# RTI-Dome.net
KiCad netlist of a schematic drawn in EAGLE
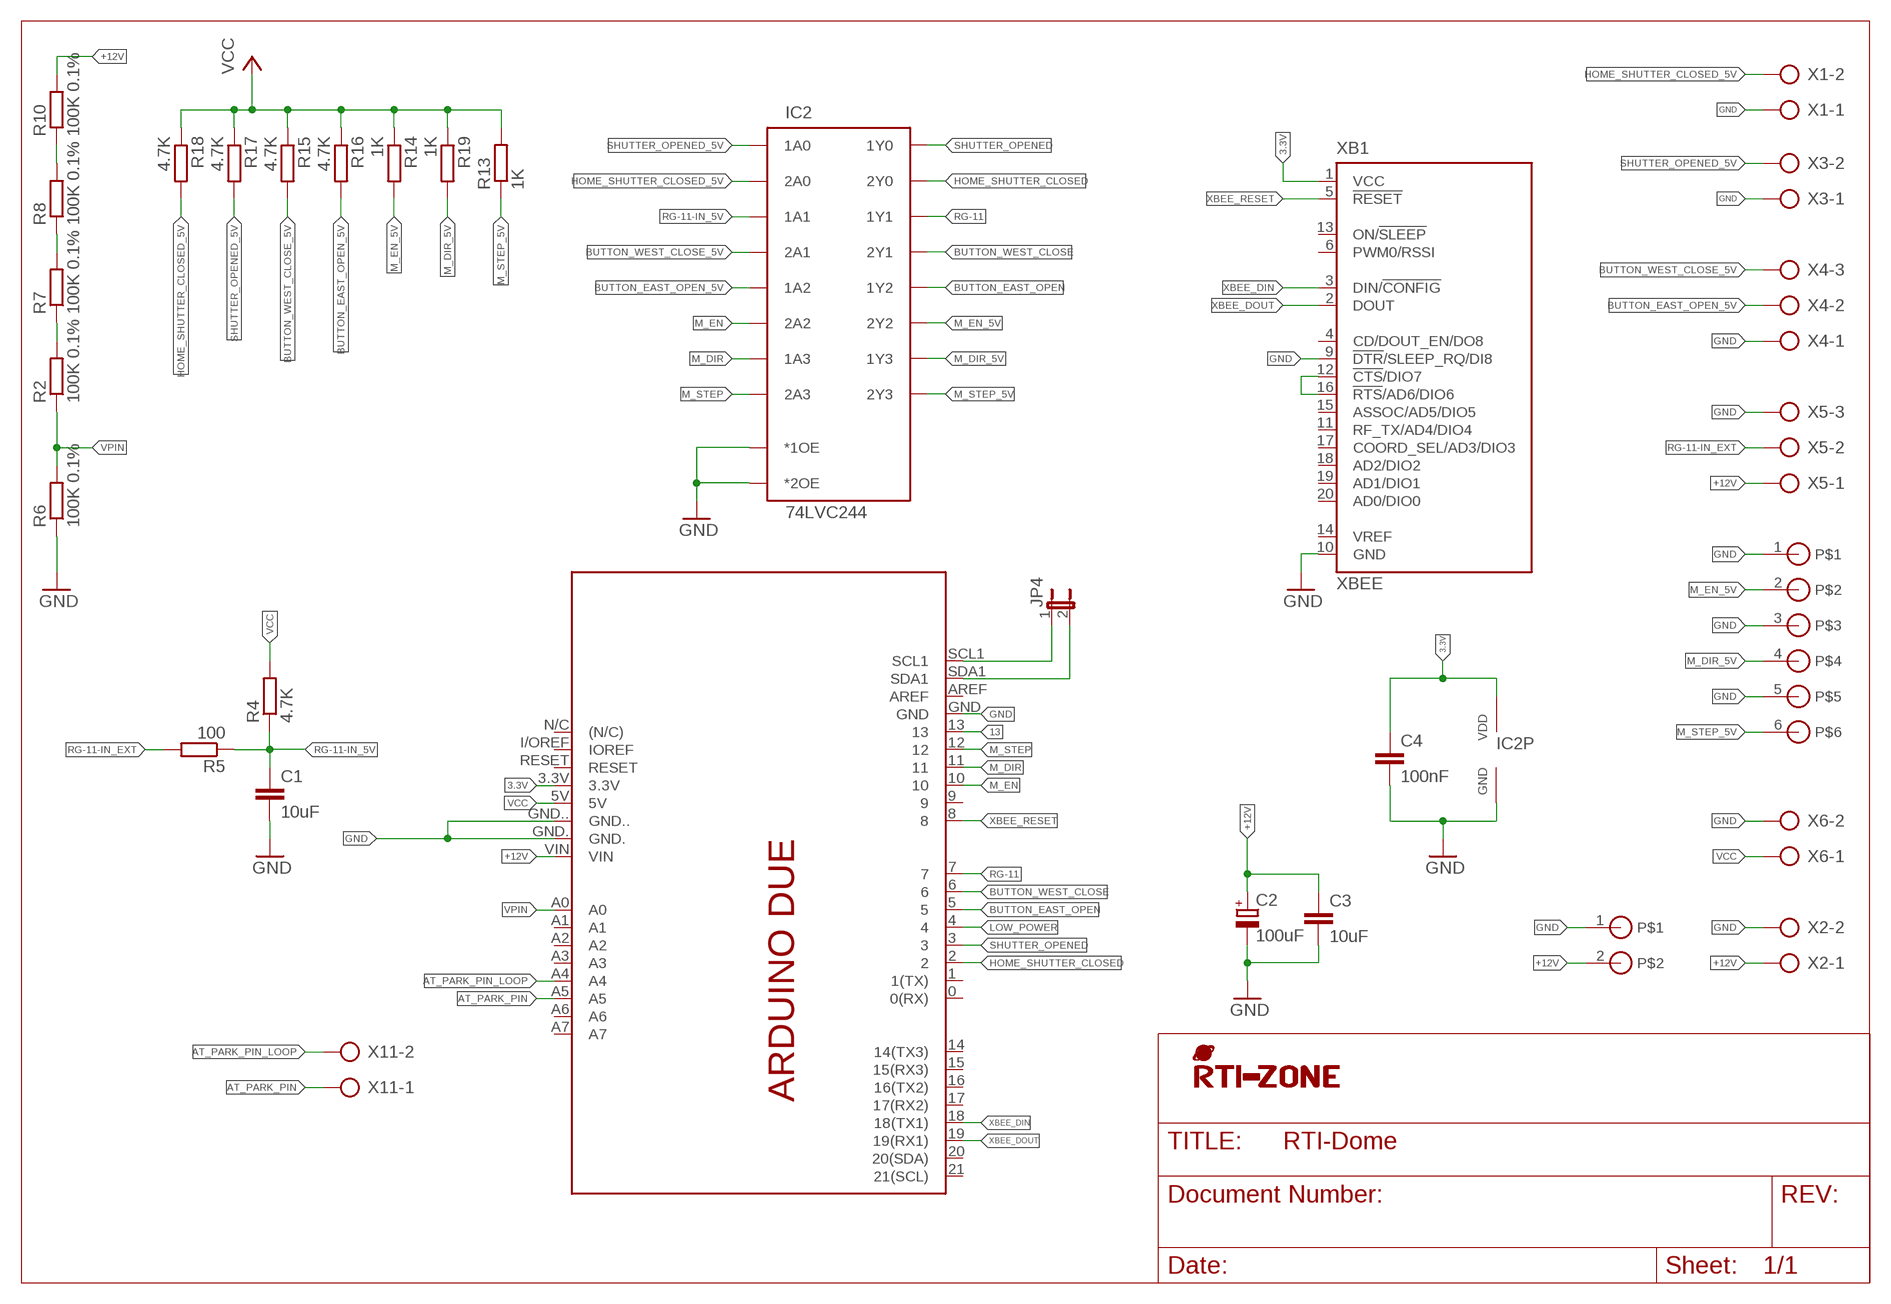
[diagram p0: schematic, sheet 1]

(export (version "E")
  (design (tool "Eeschema 10.0.6"))
  (components
    (comp (ref "C1")
      (value "10uF")
      (footprint "eagle-import:C0805")
      (libsource (lib "eagle-import") (part "C-EU'0805'"))
    )
    (comp (ref "C2")
      (value "100uF")
      (footprint "eagle-import:UD-10X10_NICHICON")
      (libsource (lib "eagle-import") (part "CPOL-EU"))
    )
    (comp (ref "C3")
      (value "10uF")
      (footprint "eagle-import:C0805")
      (libsource (lib "eagle-import") (part "C-EU'0805'"))
    )
    (comp (ref "C4")
      (value "100nF")
      (footprint "eagle-import:C0805")
      (libsource (lib "eagle-import") (part "C-EU'0805'"))
    )
    (comp (ref "IC2")
      (value "74LVC244")
      (footprint "eagle-import:TSSOP20")
      (libsource (lib "eagle-import") (part "74244LVC"))
    )
    (comp (ref "JP4")
      (value "JP1E")
      (footprint "eagle-import:JP1")
      (libsource (lib "eagle-import") (part "JP1E"))
    )
    (comp (ref "PCB1")
      (value "ARDUINO_DUE_SHIELD_SHORT")
      (footprint "eagle-import:ARDUINO_DUE_SHIELD_SHORT")
      (libsource (lib "eagle-import") (part "ARDUINO_DUE_SHIELD_SHORT"))
    )
    (comp (ref "R2")
      (value "100K 0.1%")
      (footprint "eagle-import:R0805")
      (libsource (lib "eagle-import") (part "R-EU'0805'"))
    )
    (comp (ref "R4")
      (value "4.7K")
      (footprint "eagle-import:R0805")
      (libsource (lib "eagle-import") (part "R-EU'0805'"))
    )
    (comp (ref "R5")
      (value "100")
      (footprint "eagle-import:R0805")
      (libsource (lib "eagle-import") (part "R-EU'0805'"))
    )
    (comp (ref "R6")
      (value "100K 0.1%")
      (footprint "eagle-import:R0805")
      (libsource (lib "eagle-import") (part "R-EU'0805'"))
    )
    (comp (ref "R7")
      (value "100K 0.1%")
      (footprint "eagle-import:R0805")
      (libsource (lib "eagle-import") (part "R-EU'0805'"))
    )
    (comp (ref "R8")
      (value "100K 0.1%")
      (footprint "eagle-import:R0805")
      (libsource (lib "eagle-import") (part "R-EU'0805'"))
    )
    (comp (ref "R10")
      (value "100K 0.1%")
      (footprint "eagle-import:R0805")
      (libsource (lib "eagle-import") (part "R-EU'0805'"))
    )
    (comp (ref "R13")
      (value "1K")
      (footprint "eagle-import:R0805")
      (libsource (lib "eagle-import") (part "R-EU'0805'"))
    )
    (comp (ref "R14")
      (value "1K")
      (footprint "eagle-import:R0805")
      (libsource (lib "eagle-import") (part "R-EU'0805'"))
    )
    (comp (ref "R15")
      (value "4.7K")
      (footprint "eagle-import:R0805")
      (libsource (lib "eagle-import") (part "R-EU'0805'"))
    )
    (comp (ref "R16")
      (value "4.7K")
      (footprint "eagle-import:R0805")
      (libsource (lib "eagle-import") (part "R-EU'0805'"))
    )
    (comp (ref "R17")
      (value "4.7K")
      (footprint "eagle-import:R0805")
      (libsource (lib "eagle-import") (part "R-EU'0805'"))
    )
    (comp (ref "R18")
      (value "4.7K")
      (footprint "eagle-import:R0805")
      (libsource (lib "eagle-import") (part "R-EU'0805'"))
    )
    (comp (ref "R19")
      (value "1K")
      (footprint "eagle-import:R0805")
      (libsource (lib "eagle-import") (part "R-EU'0805'"))
    )
    (comp (ref "U$2")
      (value "STL-140-2")
      (footprint "eagle-import:STL-140-2")
      (libsource (lib "eagle-import") (part "STL-140-2"))
    )
    (comp (ref "U$3")
      (value "STL-140-6")
      (footprint "eagle-import:STL-140-6")
      (libsource (lib "eagle-import") (part "STL-140-6"))
    )
    (comp (ref "U$4")
      (value "RTI-LOGO_BIG")
      (footprint "eagle-import:LOGO_BIG")
      (libsource (lib "eagle-import") (part "RTI-LOGO_BIG"))
    )
    (comp (ref "X1")
      (value "AK500/2")
      (footprint "eagle-import:AK500_2")
      (libsource (lib "eagle-import") (part "AK500/2"))
    )
    (comp (ref "X2")
      (value "AK500/2")
      (footprint "eagle-import:AK500_2")
      (libsource (lib "eagle-import") (part "AK500/2"))
    )
    (comp (ref "X3")
      (value "AK500/2")
      (footprint "eagle-import:AK500_2")
      (libsource (lib "eagle-import") (part "AK500/2"))
    )
    (comp (ref "X4")
      (value "AK500/3")
      (footprint "eagle-import:AK500_3")
      (libsource (lib "eagle-import") (part "AK500/3"))
    )
    (comp (ref "X5")
      (value "AK500/3")
      (footprint "eagle-import:AK500_3")
      (libsource (lib "eagle-import") (part "AK500/3"))
    )
    (comp (ref "X6")
      (value "AK500/2")
      (footprint "eagle-import:AK500_2")
      (libsource (lib "eagle-import") (part "AK500/2"))
    )
    (comp (ref "X11")
      (value "AK500/2")
      (footprint "eagle-import:AK500_2")
      (libsource (lib "eagle-import") (part "AK500/2"))
    )
    (comp (ref "XB1")
      (value "XBEE")
      (footprint "eagle-import:XBEE")
      (fields (field (name "MPN") "XBP24-Z7UIT-004"))
      (libsource (lib "eagle-import") (part "XBEE"))
    )
  )
  (nets
    (net (code "1") (name "+12V") (class "Default")
      (node (ref "C2") (pin "+") (pinfunction "+_+") (pintype "passive"))
      (node (ref "C3") (pin "1") (pinfunction "1_1") (pintype "passive"))
      (node (ref "PCB1") (pin "VIN") (pinfunction "VIN_VIN") (pintype "bidirectional"))
      (node (ref "R10") (pin "2") (pinfunction "2_2") (pintype "passive"))
      (node (ref "U$2") (pin "2") (pinfunction "P$2_2") (pintype "bidirectional"))
      (node (ref "X2") (pin "1") (pinfunction "KL_1") (pintype "passive"))
      (node (ref "X5") (pin "1") (pinfunction "KL_1") (pintype "passive"))
    )
    (net (code "2") (name "3.3V") (class "Default")
      (node (ref "C4") (pin "1") (pinfunction "1_1") (pintype "passive"))
      (node (ref "IC2") (pin "P$20") (pinfunction "VDD_P$20") (pintype "power_in"))
      (node (ref "PCB1") (pin "3.3V") (pinfunction "3.3V_3.3V") (pintype "bidirectional"))
      (node (ref "XB1") (pin "1") (pinfunction "VCC_1") (pintype "power_in"))
    )
    (net (code "3") (name "13") (class "Default")
      (node (ref "PCB1") (pin "13") (pinfunction "13_13") (pintype "bidirectional"))
    )
    (net (code "4") (name "AT_PARK_PIN") (class "Default")
      (node (ref "PCB1") (pin "A5") (pinfunction "A5_A5") (pintype "bidirectional"))
      (node (ref "X11") (pin "1") (pinfunction "KL_1") (pintype "passive"))
    )
    (net (code "5") (name "AT_PARK_PIN_LOOP") (class "Default")
      (node (ref "PCB1") (pin "A4") (pinfunction "A4_A4") (pintype "bidirectional"))
      (node (ref "X11") (pin "2") (pinfunction "KL_2") (pintype "passive"))
    )
    (net (code "6") (name "BUTTON_EAST_OPEN") (class "Default")
      (node (ref "IC2") (pin "P$14") (pinfunction "1Y2_P$14") (pintype "output"))
      (node (ref "PCB1") (pin "5") (pinfunction "5_5") (pintype "bidirectional"))
    )
    (net (code "7") (name "BUTTON_EAST_OPEN_5V") (class "Default")
      (node (ref "IC2") (pin "P$6") (pinfunction "1A2_P$6") (pintype "input"))
      (node (ref "R16") (pin "2") (pinfunction "2_2") (pintype "passive"))
      (node (ref "X4") (pin "2") (pinfunction "KL_2") (pintype "passive"))
    )
    (net (code "8") (name "BUTTON_WEST_CLOSE") (class "Default")
      (node (ref "IC2") (pin "P$5") (pinfunction "2Y1_P$5") (pintype "output"))
      (node (ref "PCB1") (pin "6") (pinfunction "6_6") (pintype "bidirectional"))
    )
    (net (code "9") (name "BUTTON_WEST_CLOSE_5V") (class "Default")
      (node (ref "IC2") (pin "P$15") (pinfunction "2A1_P$15") (pintype "input"))
      (node (ref "R15") (pin "2") (pinfunction "2_2") (pintype "passive"))
      (node (ref "X4") (pin "3") (pinfunction "KL_3") (pintype "passive"))
    )
    (net (code "10") (name "GND") (class "Default")
      (node (ref "C1") (pin "2") (pinfunction "2_2") (pintype "passive"))
      (node (ref "C2") (pin "-") (pinfunction "-_-") (pintype "passive"))
      (node (ref "C3") (pin "2") (pinfunction "2_2") (pintype "passive"))
      (node (ref "C4") (pin "2") (pinfunction "2_2") (pintype "passive"))
      (node (ref "IC2") (pin "P$1") (pinfunction "*1OE_P$1") (pintype "input"))
      (node (ref "IC2") (pin "P$10") (pinfunction "GND_P$10") (pintype "power_in"))
      (node (ref "IC2") (pin "P$19") (pinfunction "*2OE_P$19") (pintype "input"))
      (node (ref "PCB1") (pin "GND") (pinfunction "GND_GND") (pintype "bidirectional"))
      (node (ref "PCB1") (pin "GND.") (pinfunction "GND._GND.") (pintype "bidirectional"))
      (node (ref "PCB1") (pin "GND..") (pinfunction "GND.._GND..") (pintype "bidirectional"))
      (node (ref "R6") (pin "1") (pinfunction "1_1") (pintype "passive"))
      (node (ref "U$2") (pin "1") (pinfunction "P$1_1") (pintype "bidirectional"))
      (node (ref "U$3") (pin "1") (pinfunction "P$1_1") (pintype "bidirectional"))
      (node (ref "U$3") (pin "3") (pinfunction "P$3_3") (pintype "bidirectional"))
      (node (ref "U$3") (pin "5") (pinfunction "P$5_5") (pintype "bidirectional"))
      (node (ref "X1") (pin "1") (pinfunction "KL_1") (pintype "passive"))
      (node (ref "X2") (pin "2") (pinfunction "KL_2") (pintype "passive"))
      (node (ref "X3") (pin "1") (pinfunction "KL_1") (pintype "passive"))
      (node (ref "X4") (pin "1") (pinfunction "KL_1") (pintype "passive"))
      (node (ref "X5") (pin "3") (pinfunction "KL_3") (pintype "passive"))
      (node (ref "X6") (pin "2") (pinfunction "KL_2") (pintype "passive"))
      (node (ref "XB1") (pin "10") (pinfunction "GND_10") (pintype "power_in"))
      (node (ref "XB1") (pin "9") (pinfunction "~{DTR}/SLEEP_RQ/DI8_9") (pintype "bidirectional"))
    )
    (net (code "11") (name "HOME_SHUTTER_CLOSED") (class "Default")
      (node (ref "IC2") (pin "P$3") (pinfunction "2Y0_P$3") (pintype "output"))
      (node (ref "PCB1") (pin "2") (pinfunction "2_2") (pintype "bidirectional"))
    )
    (net (code "12") (name "HOME_SHUTTER_CLOSED_5V") (class "Default")
      (node (ref "IC2") (pin "P$17") (pinfunction "2A0_P$17") (pintype "input"))
      (node (ref "R18") (pin "2") (pinfunction "2_2") (pintype "passive"))
      (node (ref "X1") (pin "2") (pinfunction "KL_2") (pintype "passive"))
    )
    (net (code "13") (name "LOW_POWER") (class "Default")
      (node (ref "PCB1") (pin "4") (pinfunction "4_4") (pintype "bidirectional"))
    )
    (net (code "14") (name "M_DIR") (class "Default")
      (node (ref "IC2") (pin "P$8") (pinfunction "1A3_P$8") (pintype "input"))
      (node (ref "PCB1") (pin "11") (pinfunction "11_11") (pintype "bidirectional"))
    )
    (net (code "15") (name "M_DIR_5V") (class "Default")
      (node (ref "IC2") (pin "P$12") (pinfunction "1Y3_P$12") (pintype "output"))
      (node (ref "R19") (pin "2") (pinfunction "2_2") (pintype "passive"))
      (node (ref "U$3") (pin "4") (pinfunction "P$4_4") (pintype "bidirectional"))
    )
    (net (code "16") (name "M_EN") (class "Default")
      (node (ref "IC2") (pin "P$13") (pinfunction "2A2_P$13") (pintype "input"))
      (node (ref "PCB1") (pin "10") (pinfunction "10_10") (pintype "bidirectional"))
    )
    (net (code "17") (name "M_EN_5V") (class "Default")
      (node (ref "IC2") (pin "P$7") (pinfunction "2Y2_P$7") (pintype "output"))
      (node (ref "R14") (pin "2") (pinfunction "2_2") (pintype "passive"))
      (node (ref "U$3") (pin "2") (pinfunction "P$2_2") (pintype "bidirectional"))
    )
    (net (code "18") (name "M_STEP") (class "Default")
      (node (ref "IC2") (pin "P$11") (pinfunction "2A3_P$11") (pintype "input"))
      (node (ref "PCB1") (pin "12") (pinfunction "12_12") (pintype "bidirectional"))
    )
    (net (code "19") (name "M_STEP_5V") (class "Default")
      (node (ref "IC2") (pin "P$9") (pinfunction "2Y3_P$9") (pintype "output"))
      (node (ref "R13") (pin "1") (pinfunction "1_1") (pintype "passive"))
      (node (ref "U$3") (pin "6") (pinfunction "P$6_6") (pintype "bidirectional"))
    )
    (net (code "20") (name "Net-(JP4-Pad1)") (class "Default")
      (node (ref "JP4") (pin "1") (pinfunction "1_1") (pintype "passive"))
      (node (ref "PCB1") (pin "SCL1") (pinfunction "SCL1_SCL1") (pintype "bidirectional"))
    )
    (net (code "21") (name "Net-(JP4-Pad2)") (class "Default")
      (node (ref "JP4") (pin "2") (pinfunction "2_2") (pintype "passive"))
      (node (ref "PCB1") (pin "SDA1") (pinfunction "SDA1_SDA1") (pintype "bidirectional"))
    )
    (net (code "22") (name "Net-(R2-Pad2)") (class "Default")
      (node (ref "R2") (pin "2") (pinfunction "2_2") (pintype "passive"))
      (node (ref "R7") (pin "1") (pinfunction "1_1") (pintype "passive"))
    )
    (net (code "23") (name "Net-(R7-Pad2)") (class "Default")
      (node (ref "R7") (pin "2") (pinfunction "2_2") (pintype "passive"))
      (node (ref "R8") (pin "1") (pinfunction "1_1") (pintype "passive"))
    )
    (net (code "24") (name "Net-(R10-Pad1)") (class "Default")
      (node (ref "R10") (pin "1") (pinfunction "1_1") (pintype "passive"))
      (node (ref "R8") (pin "2") (pinfunction "2_2") (pintype "passive"))
    )
    (net (code "25") (name "Net-(XB1-~{CTS}{slash}DIO7)") (class "Default")
      (node (ref "XB1") (pin "12") (pinfunction "~{CTS}/DIO7_12") (pintype "bidirectional"))
      (node (ref "XB1") (pin "16") (pinfunction "~{RTS}/AD6/DIO6_16") (pintype "bidirectional"))
    )
    (net (code "26") (name "RG-11") (class "Default")
      (node (ref "IC2") (pin "P$16") (pinfunction "1Y1_P$16") (pintype "output"))
      (node (ref "PCB1") (pin "7") (pinfunction "7_7") (pintype "bidirectional"))
    )
    (net (code "27") (name "RG-11-IN_5V") (class "Default")
      (node (ref "C1") (pin "1") (pinfunction "1_1") (pintype "passive"))
      (node (ref "IC2") (pin "P$4") (pinfunction "1A1_P$4") (pintype "input"))
      (node (ref "R4") (pin "1") (pinfunction "1_1") (pintype "passive"))
      (node (ref "R5") (pin "1") (pinfunction "1_1") (pintype "passive"))
    )
    (net (code "28") (name "RG-11-IN_EXT") (class "Default")
      (node (ref "R5") (pin "2") (pinfunction "2_2") (pintype "passive"))
      (node (ref "X5") (pin "2") (pinfunction "KL_2") (pintype "passive"))
    )
    (net (code "29") (name "SHUTTER_OPENED") (class "Default")
      (node (ref "IC2") (pin "P$18") (pinfunction "1Y0_P$18") (pintype "output"))
      (node (ref "PCB1") (pin "3") (pinfunction "3_3") (pintype "bidirectional"))
    )
    (net (code "30") (name "SHUTTER_OPENED_5V") (class "Default")
      (node (ref "IC2") (pin "P$2") (pinfunction "1A0_P$2") (pintype "input"))
      (node (ref "R17") (pin "2") (pinfunction "2_2") (pintype "passive"))
      (node (ref "X3") (pin "2") (pinfunction "KL_2") (pintype "passive"))
    )
    (net (code "31") (name "VCC") (class "Default")
      (node (ref "PCB1") (pin "5V") (pinfunction "5V_5V") (pintype "bidirectional"))
      (node (ref "R13") (pin "2") (pinfunction "2_2") (pintype "passive"))
      (node (ref "R14") (pin "1") (pinfunction "1_1") (pintype "passive"))
      (node (ref "R15") (pin "1") (pinfunction "1_1") (pintype "passive"))
      (node (ref "R16") (pin "1") (pinfunction "1_1") (pintype "passive"))
      (node (ref "R17") (pin "1") (pinfunction "1_1") (pintype "passive"))
      (node (ref "R18") (pin "1") (pinfunction "1_1") (pintype "passive"))
      (node (ref "R19") (pin "1") (pinfunction "1_1") (pintype "passive"))
      (node (ref "R4") (pin "2") (pinfunction "2_2") (pintype "passive"))
      (node (ref "X6") (pin "1") (pinfunction "KL_1") (pintype "passive"))
    )
    (net (code "32") (name "VPIN") (class "Default")
      (node (ref "PCB1") (pin "A0") (pinfunction "A0_A0") (pintype "bidirectional"))
      (node (ref "R2") (pin "1") (pinfunction "1_1") (pintype "passive"))
      (node (ref "R6") (pin "2") (pinfunction "2_2") (pintype "passive"))
    )
    (net (code "33") (name "XBEE_DIN") (class "Default")
      (node (ref "PCB1") (pin "18") (pinfunction "18(TX1)_18") (pintype "bidirectional"))
      (node (ref "XB1") (pin "3") (pinfunction "DIN/~{CONFIG}_3") (pintype "input"))
    )
    (net (code "34") (name "XBEE_DOUT") (class "Default")
      (node (ref "PCB1") (pin "19") (pinfunction "19(RX1)_19") (pintype "bidirectional"))
      (node (ref "XB1") (pin "2") (pinfunction "DOUT_2") (pintype "output"))
    )
    (net (code "35") (name "XBEE_RESET") (class "Default")
      (node (ref "PCB1") (pin "8") (pinfunction "8_8") (pintype "bidirectional"))
      (node (ref "XB1") (pin "5") (pinfunction "~{RESET}_5") (pintype "input"))
    )
    (net (code "36") (name "unconnected-(PCB1-(N{slash}C)-PadN{slash}C)") (class "Default")
      (node (ref "PCB1") (pin "N/C") (pinfunction "(N/C)_N/C") (pintype "bidirectional"))
    )
    (net (code "37") (name "unconnected-(PCB1-0(RX)-Pad0)") (class "Default")
      (node (ref "PCB1") (pin "0") (pinfunction "0(RX)_0") (pintype "bidirectional"))
    )
    (net (code "38") (name "unconnected-(PCB1-1(TX)-Pad1)") (class "Default")
      (node (ref "PCB1") (pin "1") (pinfunction "1(TX)_1") (pintype "bidirectional"))
    )
    (net (code "39") (name "unconnected-(PCB1-14(TX3)-Pad14)") (class "Default")
      (node (ref "PCB1") (pin "14") (pinfunction "14(TX3)_14") (pintype "bidirectional"))
    )
    (net (code "40") (name "unconnected-(PCB1-15(RX3)-Pad15)") (class "Default")
      (node (ref "PCB1") (pin "15") (pinfunction "15(RX3)_15") (pintype "bidirectional"))
    )
    (net (code "41") (name "unconnected-(PCB1-16(TX2)-Pad16)") (class "Default")
      (node (ref "PCB1") (pin "16") (pinfunction "16(TX2)_16") (pintype "bidirectional"))
    )
    (net (code "42") (name "unconnected-(PCB1-17(RX2)-Pad17)") (class "Default")
      (node (ref "PCB1") (pin "17") (pinfunction "17(RX2)_17") (pintype "bidirectional"))
    )
    (net (code "43") (name "unconnected-(PCB1-20(SDA)-Pad20)") (class "Default")
      (node (ref "PCB1") (pin "20") (pinfunction "20(SDA)_20") (pintype "bidirectional"))
    )
    (net (code "44") (name "unconnected-(PCB1-21(SCL)-Pad21)") (class "Default")
      (node (ref "PCB1") (pin "21") (pinfunction "21(SCL)_21") (pintype "bidirectional"))
    )
    (net (code "45") (name "unconnected-(PCB1-IOREF-PadI{slash}OREF)") (class "Default")
      (node (ref "PCB1") (pin "I/OREF") (pinfunction "IOREF_I/OREF") (pintype "bidirectional"))
    )
    (net (code "46") (name "unconnected-(PCB1-Pad9)") (class "Default")
      (node (ref "PCB1") (pin "9") (pinfunction "9_9") (pintype "bidirectional"))
    )
    (net (code "47") (name "unconnected-(PCB1-PadA1)") (class "Default")
      (node (ref "PCB1") (pin "A1") (pinfunction "A1_A1") (pintype "bidirectional"))
    )
    (net (code "48") (name "unconnected-(PCB1-PadA2)") (class "Default")
      (node (ref "PCB1") (pin "A2") (pinfunction "A2_A2") (pintype "bidirectional"))
    )
    (net (code "49") (name "unconnected-(PCB1-PadA3)") (class "Default")
      (node (ref "PCB1") (pin "A3") (pinfunction "A3_A3") (pintype "bidirectional"))
    )
    (net (code "50") (name "unconnected-(PCB1-PadA6)") (class "Default")
      (node (ref "PCB1") (pin "A6") (pinfunction "A6_A6") (pintype "bidirectional"))
    )
    (net (code "51") (name "unconnected-(PCB1-PadA7)") (class "Default")
      (node (ref "PCB1") (pin "A7") (pinfunction "A7_A7") (pintype "bidirectional"))
    )
    (net (code "52") (name "unconnected-(PCB1-PadAREF)") (class "Default")
      (node (ref "PCB1") (pin "AREF") (pinfunction "AREF_AREF") (pintype "bidirectional"))
    )
    (net (code "53") (name "unconnected-(PCB1-PadRESET)") (class "Default")
      (node (ref "PCB1") (pin "RESET") (pinfunction "RESET_RESET") (pintype "bidirectional"))
    )
    (net (code "54") (name "unconnected-(XB1-AD0{slash}DIO0-Pad20)") (class "Default")
      (node (ref "XB1") (pin "20") (pinfunction "AD0/DIO0_20") (pintype "bidirectional"))
    )
    (net (code "55") (name "unconnected-(XB1-AD1{slash}DIO1-Pad19)") (class "Default")
      (node (ref "XB1") (pin "19") (pinfunction "AD1/DIO1_19") (pintype "bidirectional"))
    )
    (net (code "56") (name "unconnected-(XB1-AD2{slash}DIO2-Pad18)") (class "Default")
      (node (ref "XB1") (pin "18") (pinfunction "AD2/DIO2_18") (pintype "bidirectional"))
    )
    (net (code "57") (name "unconnected-(XB1-ASSOC{slash}AD5{slash}DIO5-Pad15)") (class "Default")
      (node (ref "XB1") (pin "15") (pinfunction "ASSOC/AD5/DIO5_15") (pintype "bidirectional"))
    )
    (net (code "58") (name "unconnected-(XB1-CD{slash}DOUT_EN{slash}DO8-Pad4)") (class "Default")
      (node (ref "XB1") (pin "4") (pinfunction "CD/DOUT_EN/DO8_4") (pintype "output"))
    )
    (net (code "59") (name "unconnected-(XB1-COORD_SEL{slash}AD3{slash}DIO3-Pad17)") (class "Default")
      (node (ref "XB1") (pin "17") (pinfunction "COORD_SEL/AD3/DIO3_17") (pintype "bidirectional"))
    )
    (net (code "60") (name "unconnected-(XB1-ON{slash}~{SLEEP}-Pad13)") (class "Default")
      (node (ref "XB1") (pin "13") (pinfunction "ON/~{SLEEP}_13") (pintype "output"))
    )
    (net (code "61") (name "unconnected-(XB1-PWM0{slash}RSSI-Pad6)") (class "Default")
      (node (ref "XB1") (pin "6") (pinfunction "PWM0/RSSI_6") (pintype "output"))
    )
    (net (code "62") (name "unconnected-(XB1-RF_TX{slash}AD4{slash}DIO4-Pad11)") (class "Default")
      (node (ref "XB1") (pin "11") (pinfunction "RF_TX/AD4/DIO4_11") (pintype "bidirectional"))
    )
    (net (code "63") (name "unconnected-(XB1-VREF-Pad14)") (class "Default")
      (node (ref "XB1") (pin "14") (pinfunction "VREF_14") (pintype "input"))
    )
  )
)
